# Source_dc_voltage_and_dc_current_block.net
KiCad netlist of a schematic drawn in EAGLE
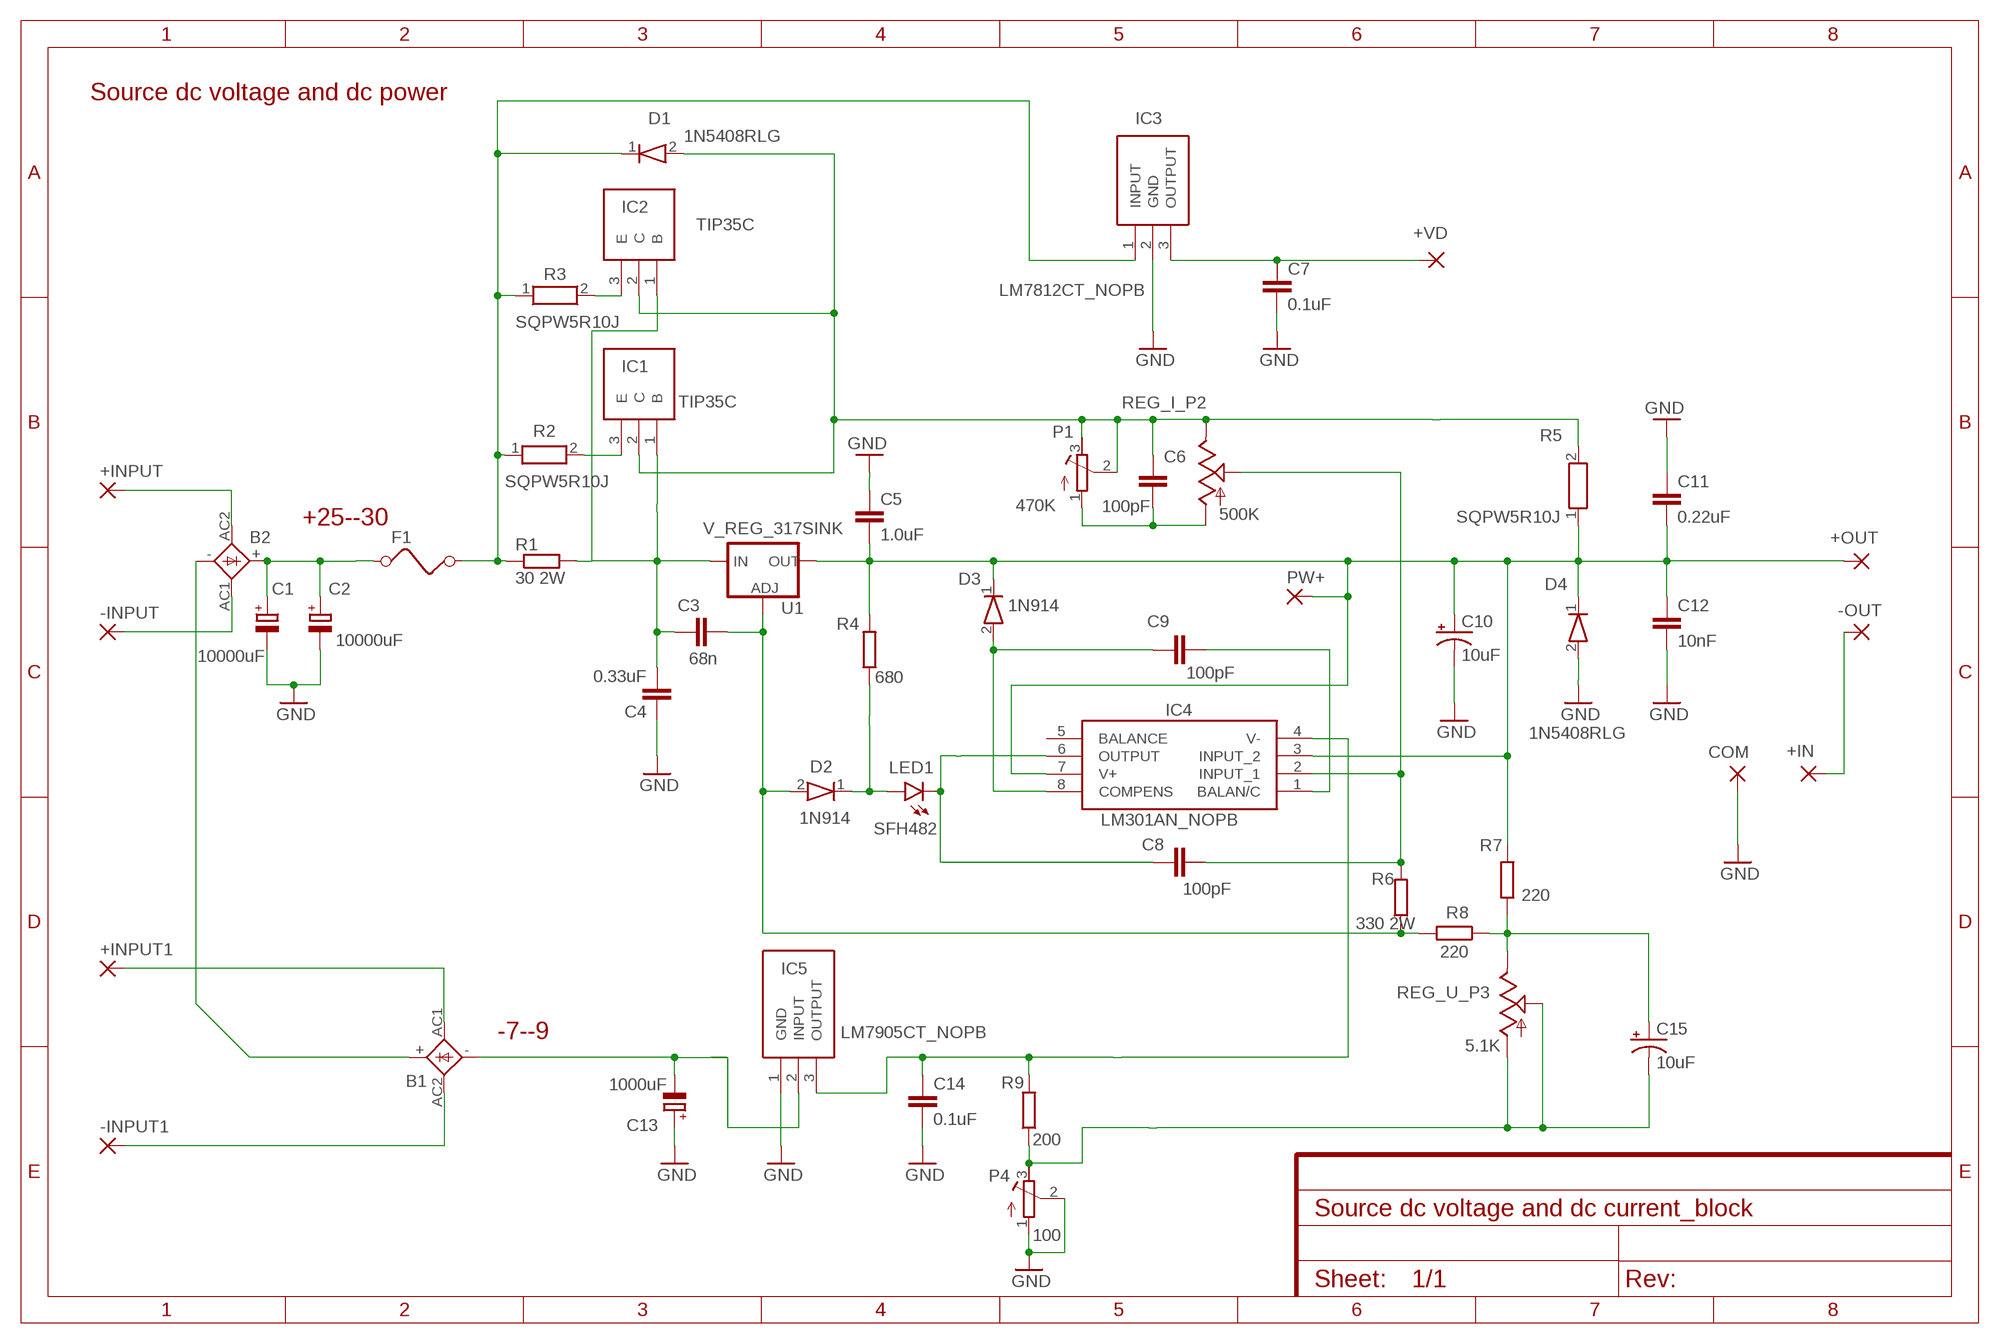
[diagram p0: schematic, sheet 1]

(export (version "E")
  (design (tool "Eeschema 10.0.6"))
  (components
    (comp (ref "+IN")
      (value "3,17/1,3")
      (footprint "eagle-import:3,17_1,3")
      (libsource (lib "eagle-import") (part "3,17/1,3"))
    )
    (comp (ref "+INPUT")
      (value "3,17/1,3")
      (footprint "eagle-import:3,17_1,3")
      (libsource (lib "eagle-import") (part "3,17/1,3"))
    )
    (comp (ref "+INPUT1")
      (value "3,17/1,3")
      (footprint "eagle-import:3,17_1,3")
      (libsource (lib "eagle-import") (part "3,17/1,3"))
    )
    (comp (ref "+OUT")
      (value "3,17/1,3")
      (footprint "eagle-import:3,17_1,3")
      (libsource (lib "eagle-import") (part "3,17/1,3"))
    )
    (comp (ref "+VD")
      (value "3,81/1,4")
      (footprint "eagle-import:3,81_1,4")
      (libsource (lib "eagle-import") (part "3,81/1,4"))
    )
    (comp (ref "-INPUT")
      (value "3,17/1,3")
      (footprint "eagle-import:3,17_1,3")
      (libsource (lib "eagle-import") (part "3,17/1,3"))
    )
    (comp (ref "-INPUT1")
      (value "3,17/1,3")
      (footprint "eagle-import:3,17_1,3")
      (libsource (lib "eagle-import") (part "3,17/1,3"))
    )
    (comp (ref "-OUT")
      (value "3,17/1,3")
      (footprint "eagle-import:3,17_1,3")
      (libsource (lib "eagle-import") (part "3,17/1,3"))
    )
    (comp (ref "B1")
      (value "FBU4")
      (footprint "eagle-import:FBU4")
      (libsource (lib "eagle-import") (part "FBU4"))
    )
    (comp (ref "B2")
      (value "FBU4")
      (footprint "eagle-import:FBU4")
      (libsource (lib "eagle-import") (part "FBU4"))
    )
    (comp (ref "C1")
      (value "10000uF")
      (footprint "eagle-import:EB30D")
      (libsource (lib "eagle-import") (part "CPOL-EUE10-30"))
    )
    (comp (ref "C2")
      (value "10000uF")
      (footprint "eagle-import:EB30D")
      (libsource (lib "eagle-import") (part "CPOL-EUE10-30"))
    )
    (comp (ref "C3")
      (value "68n")
      (footprint "eagle-import:C050-025X075")
      (libsource (lib "eagle-import") (part "C-EU050-025X075"))
    )
    (comp (ref "C4")
      (value "0.33uF")
      (footprint "eagle-import:C5B2.5")
      (libsource (lib "eagle-import") (part "C5/2.5"))
    )
    (comp (ref "C5")
      (value "1.0uF")
      (footprint "eagle-import:C050-025X075")
      (libsource (lib "eagle-import") (part "C-EU050-025X075"))
    )
    (comp (ref "C6")
      (value "100pF")
      (footprint "eagle-import:C5B2.5")
      (libsource (lib "eagle-import") (part "C5/2.5"))
    )
    (comp (ref "C7")
      (value "0.1uF")
      (footprint "eagle-import:C5B2.5")
      (libsource (lib "eagle-import") (part "C5/2.5"))
    )
    (comp (ref "C8")
      (value "100pF")
      (footprint "eagle-import:C5B2.5")
      (libsource (lib "eagle-import") (part "C5/2.5"))
    )
    (comp (ref "C9")
      (value "100pF")
      (footprint "eagle-import:C5B2.5")
      (libsource (lib "eagle-import") (part "C5/2.5"))
    )
    (comp (ref "C10")
      (value "10uF")
      (footprint "eagle-import:CPOL-RADIAL-2.5MM-5MM")
      (libsource (lib "eagle-import") (part "10UF-POLAR-RADIAL-2.5MM-25V-20%"))
    )
    (comp (ref "C11")
      (value "0.22uF")
      (footprint "eagle-import:C5B2.5")
      (libsource (lib "eagle-import") (part "C5/2.5"))
    )
    (comp (ref "C12")
      (value "10nF")
      (footprint "eagle-import:C5B2.5")
      (libsource (lib "eagle-import") (part "C5/2.5"))
    )
    (comp (ref "C13")
      (value "1000uF")
      (footprint "eagle-import:EB22,5D")
      (libsource (lib "eagle-import") (part "CPOL-EUE10-22.5"))
    )
    (comp (ref "C14")
      (value "0.1uF")
      (footprint "eagle-import:C5B2.5")
      (libsource (lib "eagle-import") (part "C5/2.5"))
    )
    (comp (ref "C15")
      (value "10uF")
      (footprint "eagle-import:CPOL-RADIAL-2.5MM-5MM")
      (libsource (lib "eagle-import") (part "10UF-POLAR-RADIAL-2.5MM-25V-20%"))
    )
    (comp (ref "COM")
      (value "3,17/1,3")
      (footprint "eagle-import:3,17_1,3")
      (libsource (lib "eagle-import") (part "3,17/1,3"))
    )
    (comp (ref "D1")
      (value "1N5408RLG")
      (footprint "eagle-import:DIOAD2860W130L840D505")
      (fields (field (name "MOUSER_PART_NUMBER") "863-1N5408RLG"))
      (libsource (lib "eagle-import") (part "1N5408RLG"))
    )
    (comp (ref "D2")
      (value "1N914")
      (footprint "eagle-import:DIOAD1068W53L380D172")
      (fields (field (name "MOUSER_PART_NUMBER") "512-1N914"))
      (libsource (lib "eagle-import") (part "1N914"))
    )
    (comp (ref "D3")
      (value "1N914")
      (footprint "eagle-import:DIOAD1068W53L380D172")
      (fields (field (name "MOUSER_PART_NUMBER") "512-1N914"))
      (libsource (lib "eagle-import") (part "1N914"))
    )
    (comp (ref "D4")
      (value "1N5408RLG")
      (footprint "eagle-import:DIOAD2860W130L840D505")
      (fields (field (name "MOUSER_PART_NUMBER") "863-1N5408RLG"))
      (libsource (lib "eagle-import") (part "1N5408RLG"))
    )
    (comp (ref "F1")
      (value "FUSE")
      (footprint "eagle-import:FUSE")
      (libsource (lib "eagle-import") (part "FUSE"))
    )
    (comp (ref "IC1")
      (value "TIP35C")
      (footprint "eagle-import:TO545P515X1560X2445-3P")
      (fields (field (name "MOUSER_PART_NUMBER") "511-TIP35C"))
      (libsource (lib "eagle-import") (part "TIP35C"))
    )
    (comp (ref "IC2")
      (value "TIP35C")
      (footprint "eagle-import:TO545P515X1560X2445-3P")
      (fields (field (name "MOUSER_PART_NUMBER") "511-TIP35C"))
      (libsource (lib "eagle-import") (part "TIP35C"))
    )
    (comp (ref "IC3")
      (value "LM7812CT_NOPB")
      (footprint "eagle-import:TO254P470X1028X1955-3P")
      (fields
        (field (name "ARROW_PART_NUMBER") "LM7812CT/NOPB")
        (field (name "MOUSER_PART_NUMBER") "926-LM7812CT/NOPB")
      )
      (libsource (lib "eagle-import") (part "LM7812CT_NOPB"))
    )
    (comp (ref "IC4")
      (value "LM301AN_NOPB")
      (footprint "eagle-import:DIP794W53P254L959H508Q8N")
      (fields
        (field (name "ARROW_PART_NUMBER") "LM301AN/NOPB")
        (field (name "MOUSER_PART_NUMBER") "926-LM301AN/NOPB")
      )
      (libsource (lib "eagle-import") (part "LM301AN_NOPB"))
    )
    (comp (ref "IC5")
      (value "LM7905CT_NOPB")
      (footprint "eagle-import:TO254P470X1028X1955-3P")
      (fields
        (field (name "ARROW_PART_NUMBER") "LM7905CT/NOPB")
        (field (name "MOUSER_PART_NUMBER") "926-LM7905CT/NOPB")
      )
      (libsource (lib "eagle-import") (part "LM7905CT_NOPB"))
    )
    (comp (ref "LED1")
      (value "SFH482")
      (footprint "eagle-import:SFH482")
      (libsource (lib "eagle-import") (part "SFH482"))
    )
    (comp (ref "P1")
      (value "470K")
      (footprint "eagle-import:RTRIM3296W")
      (libsource (lib "eagle-import") (part "R-TRIMM3296W"))
    )
    (comp (ref "P4")
      (value "100")
      (footprint "eagle-import:RTRIM3296W")
      (libsource (lib "eagle-import") (part "R-TRIMM3296W"))
    )
    (comp (ref "PW+")
      (value "3,17/1,3")
      (footprint "eagle-import:3,17_1,3")
      (libsource (lib "eagle-import") (part "3,17/1,3"))
    )
    (comp (ref "R1")
      (value "30 2W")
      (footprint "eagle-import:0207_10")
      (libsource (lib "eagle-import") (part "R-EU_0207/10"))
    )
    (comp (ref "R2")
      (value "SQPW5R10J")
      (footprint "eagle-import:RESAD6200W85L2200D1000")
      (fields (field (name "MOUSER_PART_NUMBER") "279-SQPW5R10J"))
      (libsource (lib "eagle-import") (part "SQPW5R10J"))
    )
    (comp (ref "R3")
      (value "SQPW5R10J")
      (footprint "eagle-import:RESAD6200W85L2200D1000")
      (fields (field (name "MOUSER_PART_NUMBER") "279-SQPW5R10J"))
      (libsource (lib "eagle-import") (part "SQPW5R10J"))
    )
    (comp (ref "R4")
      (value "680")
      (footprint "eagle-import:R1206")
      (libsource (lib "eagle-import") (part "R-EU_R1206"))
    )
    (comp (ref "R5")
      (value "SQPW5R10J")
      (footprint "eagle-import:RESAD6200W85L2200D1000")
      (fields (field (name "MOUSER_PART_NUMBER") "279-SQPW5R10J"))
      (libsource (lib "eagle-import") (part "SQPW5R10J"))
    )
    (comp (ref "R6")
      (value "330 2W")
      (footprint "eagle-import:0207_10")
      (libsource (lib "eagle-import") (part "R-EU_0207/10"))
    )
    (comp (ref "R7")
      (value "220")
      (footprint "eagle-import:M1206")
      (libsource (lib "eagle-import") (part "R-EU_M1206"))
    )
    (comp (ref "R8")
      (value "220")
      (footprint "eagle-import:M1206")
      (libsource (lib "eagle-import") (part "R-EU_M1206"))
    )
    (comp (ref "R9")
      (value "200")
      (footprint "eagle-import:M1206")
      (libsource (lib "eagle-import") (part "R-EU_M1206"))
    )
    (comp (ref "REG_I_P2")
      (value "500K")
      (footprint "eagle-import:POT_ALPHA_RV16AF-20")
      (libsource (lib "eagle-import") (part "POT-RV16AF-20"))
    )
    (comp (ref "REG_U_P3")
      (value "5.1K")
      (footprint "eagle-import:POT_ALPHA_RV16AF-20")
      (libsource (lib "eagle-import") (part "POT-RV16AF-20"))
    )
    (comp (ref "U1")
      (value "V_REG_317SINK")
      (footprint "eagle-import:TO220-ADJ")
      (libsource (lib "eagle-import") (part "V_REG_317SINK"))
    )
  )
  (nets
    (net (code "1") (name "GND") (class "Default")
      (node (ref "C1") (pin "-") (pinfunction "-_-") (pintype "passive"))
      (node (ref "C10") (pin "2") (pinfunction "-_2") (pintype "passive"))
      (node (ref "C11") (pin "1") (pinfunction "1_1") (pintype "passive"))
      (node (ref "C12") (pin "2") (pinfunction "2_2") (pintype "passive"))
      (node (ref "C13") (pin "+") (pinfunction "+_+") (pintype "passive"))
      (node (ref "C14") (pin "2") (pinfunction "2_2") (pintype "passive"))
      (node (ref "C2") (pin "-") (pinfunction "-_-") (pintype "passive"))
      (node (ref "C4") (pin "1") (pinfunction "1_1") (pintype "passive"))
      (node (ref "C5") (pin "1") (pinfunction "1_1") (pintype "passive"))
      (node (ref "C7") (pin "2") (pinfunction "2_2") (pintype "passive"))
      (node (ref "COM") (pin "1") (pinfunction "P_1") (pintype "passive"))
      (node (ref "D4") (pin "2") (pinfunction "A_2") (pintype "bidirectional"))
      (node (ref "IC3") (pin "2") (pinfunction "GND_2") (pintype "bidirectional"))
      (node (ref "IC5") (pin "1") (pinfunction "GND_1") (pintype "bidirectional"))
      (node (ref "P4") (pin "1") (pinfunction "A_1") (pintype "passive"))
      (node (ref "P4") (pin "2") (pinfunction "S_2") (pintype "passive"))
    )
    (net (code "2") (name "Net-(+IN-P)") (class "Default")
      (node (ref "+IN") (pin "1") (pinfunction "P_1") (pintype "passive"))
      (node (ref "-OUT") (pin "1") (pinfunction "P_1") (pintype "passive"))
    )
    (net (code "3") (name "Net-(+INPUT-P)") (class "Default")
      (node (ref "+INPUT") (pin "1") (pinfunction "P_1") (pintype "passive"))
      (node (ref "B2") (pin "AC2") (pinfunction "AC1_AC2") (pintype "passive"))
    )
    (net (code "4") (name "Net-(+INPUT1-P)") (class "Default")
      (node (ref "+INPUT1") (pin "1") (pinfunction "P_1") (pintype "passive"))
      (node (ref "B1") (pin "AC1") (pinfunction "AC2_AC1") (pintype "passive"))
    )
    (net (code "5") (name "Net-(+OUT-P)") (class "Default")
      (node (ref "+OUT") (pin "1") (pinfunction "P_1") (pintype "passive"))
      (node (ref "C10") (pin "1") (pinfunction "+_1") (pintype "passive"))
      (node (ref "C11") (pin "2") (pinfunction "2_2") (pintype "passive"))
      (node (ref "C12") (pin "1") (pinfunction "1_1") (pintype "passive"))
      (node (ref "C5") (pin "2") (pinfunction "2_2") (pintype "passive"))
      (node (ref "D3") (pin "1") (pinfunction "K_1") (pintype "bidirectional"))
      (node (ref "D4") (pin "1") (pinfunction "K_1") (pintype "bidirectional"))
      (node (ref "IC4") (pin "3") (pinfunction "INPUT_2_3") (pintype "bidirectional"))
      (node (ref "IC4") (pin "7") (pinfunction "V+_7") (pintype "bidirectional"))
      (node (ref "PW+") (pin "1") (pinfunction "P_1") (pintype "passive"))
      (node (ref "R4") (pin "2") (pinfunction "2_2") (pintype "passive"))
      (node (ref "R5") (pin "1") (pinfunction "1_1") (pintype "bidirectional"))
      (node (ref "R7") (pin "2") (pinfunction "2_2") (pintype "passive"))
      (node (ref "U1") (pin "OUT") (pinfunction "OUT_OUT") (pintype "output"))
    )
    (net (code "6") (name "Net-(+VD-P)") (class "Default")
      (node (ref "+VD") (pin "1") (pinfunction "P_1") (pintype "passive"))
      (node (ref "C7") (pin "1") (pinfunction "1_1") (pintype "passive"))
      (node (ref "IC3") (pin "3") (pinfunction "OUTPUT_3") (pintype "bidirectional"))
    )
    (net (code "7") (name "Net-(-INPUT-P)") (class "Default")
      (node (ref "-INPUT") (pin "1") (pinfunction "P_1") (pintype "passive"))
      (node (ref "B2") (pin "AC1") (pinfunction "AC2_AC1") (pintype "passive"))
    )
    (net (code "8") (name "Net-(-INPUT1-P)") (class "Default")
      (node (ref "-INPUT1") (pin "1") (pinfunction "P_1") (pintype "passive"))
      (node (ref "B1") (pin "AC2") (pinfunction "AC1_AC2") (pintype "passive"))
    )
    (net (code "9") (name "Net-(B1-Pad+)") (class "Default")
      (node (ref "B1") (pin "+") (pinfunction "+_+") (pintype "passive"))
      (node (ref "B2") (pin "-") (pinfunction "-_-") (pintype "passive"))
    )
    (net (code "10") (name "Net-(B2-Pad+)") (class "Default")
      (node (ref "B2") (pin "+") (pinfunction "+_+") (pintype "passive"))
      (node (ref "C1") (pin "+") (pinfunction "+_+") (pintype "passive"))
      (node (ref "C2") (pin "+") (pinfunction "+_+") (pintype "passive"))
      (node (ref "F1") (pin "1") (pinfunction "1_1") (pintype "passive"))
    )
    (net (code "11") (name "Net-(C15-+)") (class "Default")
      (node (ref "C15") (pin "1") (pinfunction "+_1") (pintype "passive"))
      (node (ref "R7") (pin "1") (pinfunction "1_1") (pintype "passive"))
      (node (ref "R8") (pin "1") (pinfunction "1_1") (pintype "passive"))
      (node (ref "REG_U_P3") (pin "3") (pinfunction "E_3") (pintype "passive"))
    )
    (net (code "12") (name "Net-(C15--)") (class "Default")
      (node (ref "C15") (pin "2") (pinfunction "-_2") (pintype "passive"))
      (node (ref "P4") (pin "3") (pinfunction "E_3") (pintype "passive"))
      (node (ref "R9") (pin "1") (pinfunction "1_1") (pintype "passive"))
      (node (ref "REG_U_P3") (pin "1") (pinfunction "A_1") (pintype "passive"))
      (node (ref "REG_U_P3") (pin "2") (pinfunction "S_2") (pintype "passive"))
    )
    (net (code "13") (name "Net-(D1-A)") (class "Default")
      (node (ref "C6") (pin "1") (pinfunction "1_1") (pintype "passive"))
      (node (ref "D1") (pin "2") (pinfunction "A_2") (pintype "bidirectional"))
      (node (ref "IC1") (pin "2") (pinfunction "C_2") (pintype "bidirectional"))
      (node (ref "IC2") (pin "2") (pinfunction "C_2") (pintype "bidirectional"))
      (node (ref "P1") (pin "2") (pinfunction "S_2") (pintype "passive"))
      (node (ref "P1") (pin "3") (pinfunction "E_3") (pintype "passive"))
      (node (ref "R5") (pin "2") (pinfunction "2_2") (pintype "bidirectional"))
      (node (ref "REG_I_P2") (pin "3") (pinfunction "E_3") (pintype "passive"))
    )
    (net (code "14") (name "Net-(D1-K)") (class "Default")
      (node (ref "D1") (pin "1") (pinfunction "K_1") (pintype "bidirectional"))
      (node (ref "F1") (pin "2") (pinfunction "2_2") (pintype "passive"))
      (node (ref "IC3") (pin "1") (pinfunction "INPUT_1") (pintype "bidirectional"))
      (node (ref "R1") (pin "1") (pinfunction "1_1") (pintype "passive"))
      (node (ref "R2") (pin "1") (pinfunction "1_1") (pintype "bidirectional"))
      (node (ref "R3") (pin "1") (pinfunction "1_1") (pintype "bidirectional"))
    )
    (net (code "15") (name "Net-(D2-A)") (class "Default")
      (node (ref "C3") (pin "2") (pinfunction "2_2") (pintype "passive"))
      (node (ref "D2") (pin "2") (pinfunction "A_2") (pintype "bidirectional"))
      (node (ref "R6") (pin "1") (pinfunction "1_1") (pintype "passive"))
      (node (ref "R8") (pin "2") (pinfunction "2_2") (pintype "passive"))
      (node (ref "U1") (pin "ADJ") (pinfunction "ADJ_ADJ") (pintype "input"))
    )
    (net (code "16") (name "Net-(D2-K)") (class "Default")
      (node (ref "D2") (pin "1") (pinfunction "K_1") (pintype "bidirectional"))
      (node (ref "LED1") (pin "A") (pinfunction "A_A") (pintype "passive"))
      (node (ref "R4") (pin "1") (pinfunction "1_1") (pintype "passive"))
    )
    (net (code "17") (name "Net-(D3-A)") (class "Default")
      (node (ref "C9") (pin "1") (pinfunction "1_1") (pintype "passive"))
      (node (ref "D3") (pin "2") (pinfunction "A_2") (pintype "bidirectional"))
      (node (ref "IC4") (pin "8") (pinfunction "COMPENS_8") (pintype "bidirectional"))
    )
    (net (code "18") (name "Net-(IC1-B)") (class "Default")
      (node (ref "C3") (pin "1") (pinfunction "1_1") (pintype "passive"))
      (node (ref "C4") (pin "2") (pinfunction "2_2") (pintype "passive"))
      (node (ref "IC1") (pin "1") (pinfunction "B_1") (pintype "bidirectional"))
      (node (ref "IC2") (pin "1") (pinfunction "B_1") (pintype "bidirectional"))
      (node (ref "R1") (pin "2") (pinfunction "2_2") (pintype "passive"))
      (node (ref "U1") (pin "IN") (pinfunction "IN_IN") (pintype "input"))
    )
    (net (code "19") (name "Net-(IC1-E)") (class "Default")
      (node (ref "IC1") (pin "3") (pinfunction "E_3") (pintype "bidirectional"))
      (node (ref "R2") (pin "2") (pinfunction "2_2") (pintype "bidirectional"))
    )
    (net (code "20") (name "Net-(IC2-E)") (class "Default")
      (node (ref "IC2") (pin "3") (pinfunction "E_3") (pintype "bidirectional"))
      (node (ref "R3") (pin "2") (pinfunction "2_2") (pintype "bidirectional"))
    )
    (net (code "21") (name "Net-(IC4-BALAN{slash}C)") (class "Default")
      (node (ref "C9") (pin "2") (pinfunction "2_2") (pintype "passive"))
      (node (ref "IC4") (pin "1") (pinfunction "BALAN/C_1") (pintype "bidirectional"))
    )
    (net (code "22") (name "Net-(IC4-INPUT_1)") (class "Default")
      (node (ref "C8") (pin "2") (pinfunction "2_2") (pintype "passive"))
      (node (ref "IC4") (pin "2") (pinfunction "INPUT_1_2") (pintype "bidirectional"))
      (node (ref "R6") (pin "2") (pinfunction "2_2") (pintype "passive"))
      (node (ref "REG_I_P2") (pin "2") (pinfunction "S_2") (pintype "passive"))
    )
    (net (code "23") (name "Net-(IC4-OUTPUT)") (class "Default")
      (node (ref "C8") (pin "1") (pinfunction "1_1") (pintype "passive"))
      (node (ref "IC4") (pin "6") (pinfunction "OUTPUT_6") (pintype "bidirectional"))
      (node (ref "LED1") (pin "K") (pinfunction "C_K") (pintype "passive"))
    )
    (net (code "24") (name "Net-(IC4-V-)") (class "Default")
      (node (ref "C14") (pin "1") (pinfunction "1_1") (pintype "passive"))
      (node (ref "IC4") (pin "4") (pinfunction "V-_4") (pintype "bidirectional"))
      (node (ref "IC5") (pin "3") (pinfunction "OUTPUT_3") (pintype "bidirectional"))
      (node (ref "R9") (pin "2") (pinfunction "2_2") (pintype "passive"))
    )
    (net (code "25") (name "Net-(IC5-INPUT)") (class "Default")
      (node (ref "B1") (pin "-") (pinfunction "-_-") (pintype "passive"))
      (node (ref "C13") (pin "-") (pinfunction "-_-") (pintype "passive"))
      (node (ref "IC5") (pin "2") (pinfunction "INPUT_2") (pintype "bidirectional"))
    )
    (net (code "26") (name "Net-(P1-A)") (class "Default")
      (node (ref "C6") (pin "2") (pinfunction "2_2") (pintype "passive"))
      (node (ref "P1") (pin "1") (pinfunction "A_1") (pintype "passive"))
      (node (ref "REG_I_P2") (pin "1") (pinfunction "A_1") (pintype "passive"))
    )
    (net (code "27") (name "unconnected-(IC4-BALANCE-Pad5)") (class "Default")
      (node (ref "IC4") (pin "5") (pinfunction "BALANCE_5") (pintype "bidirectional"))
    )
  )
)
